# FindMe_Hub.net
KiCad netlist of a schematic drawn in EAGLE
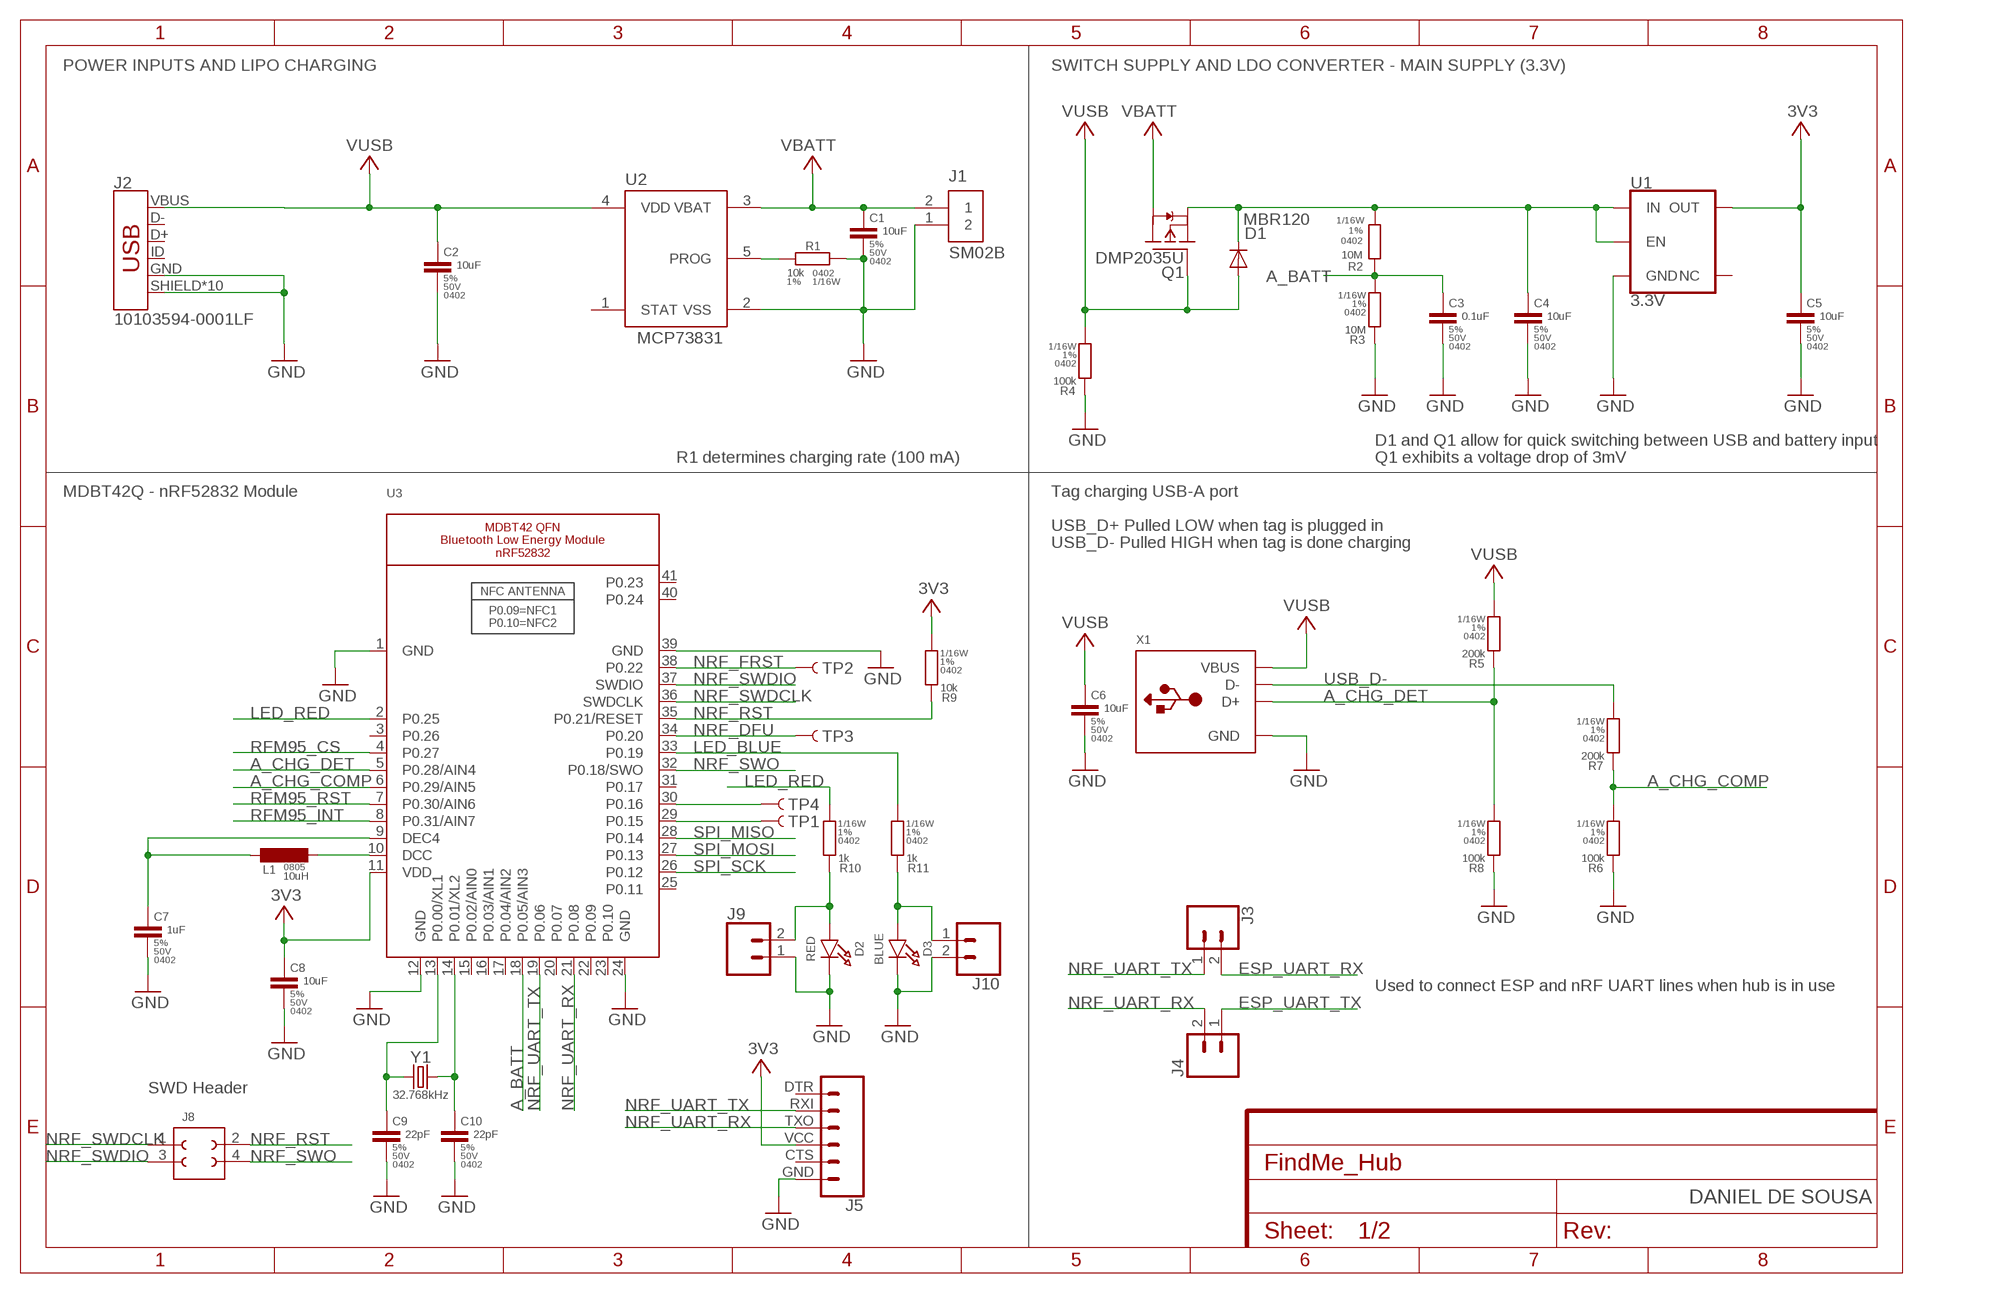
[diagram p0: schematic, sheet 1]
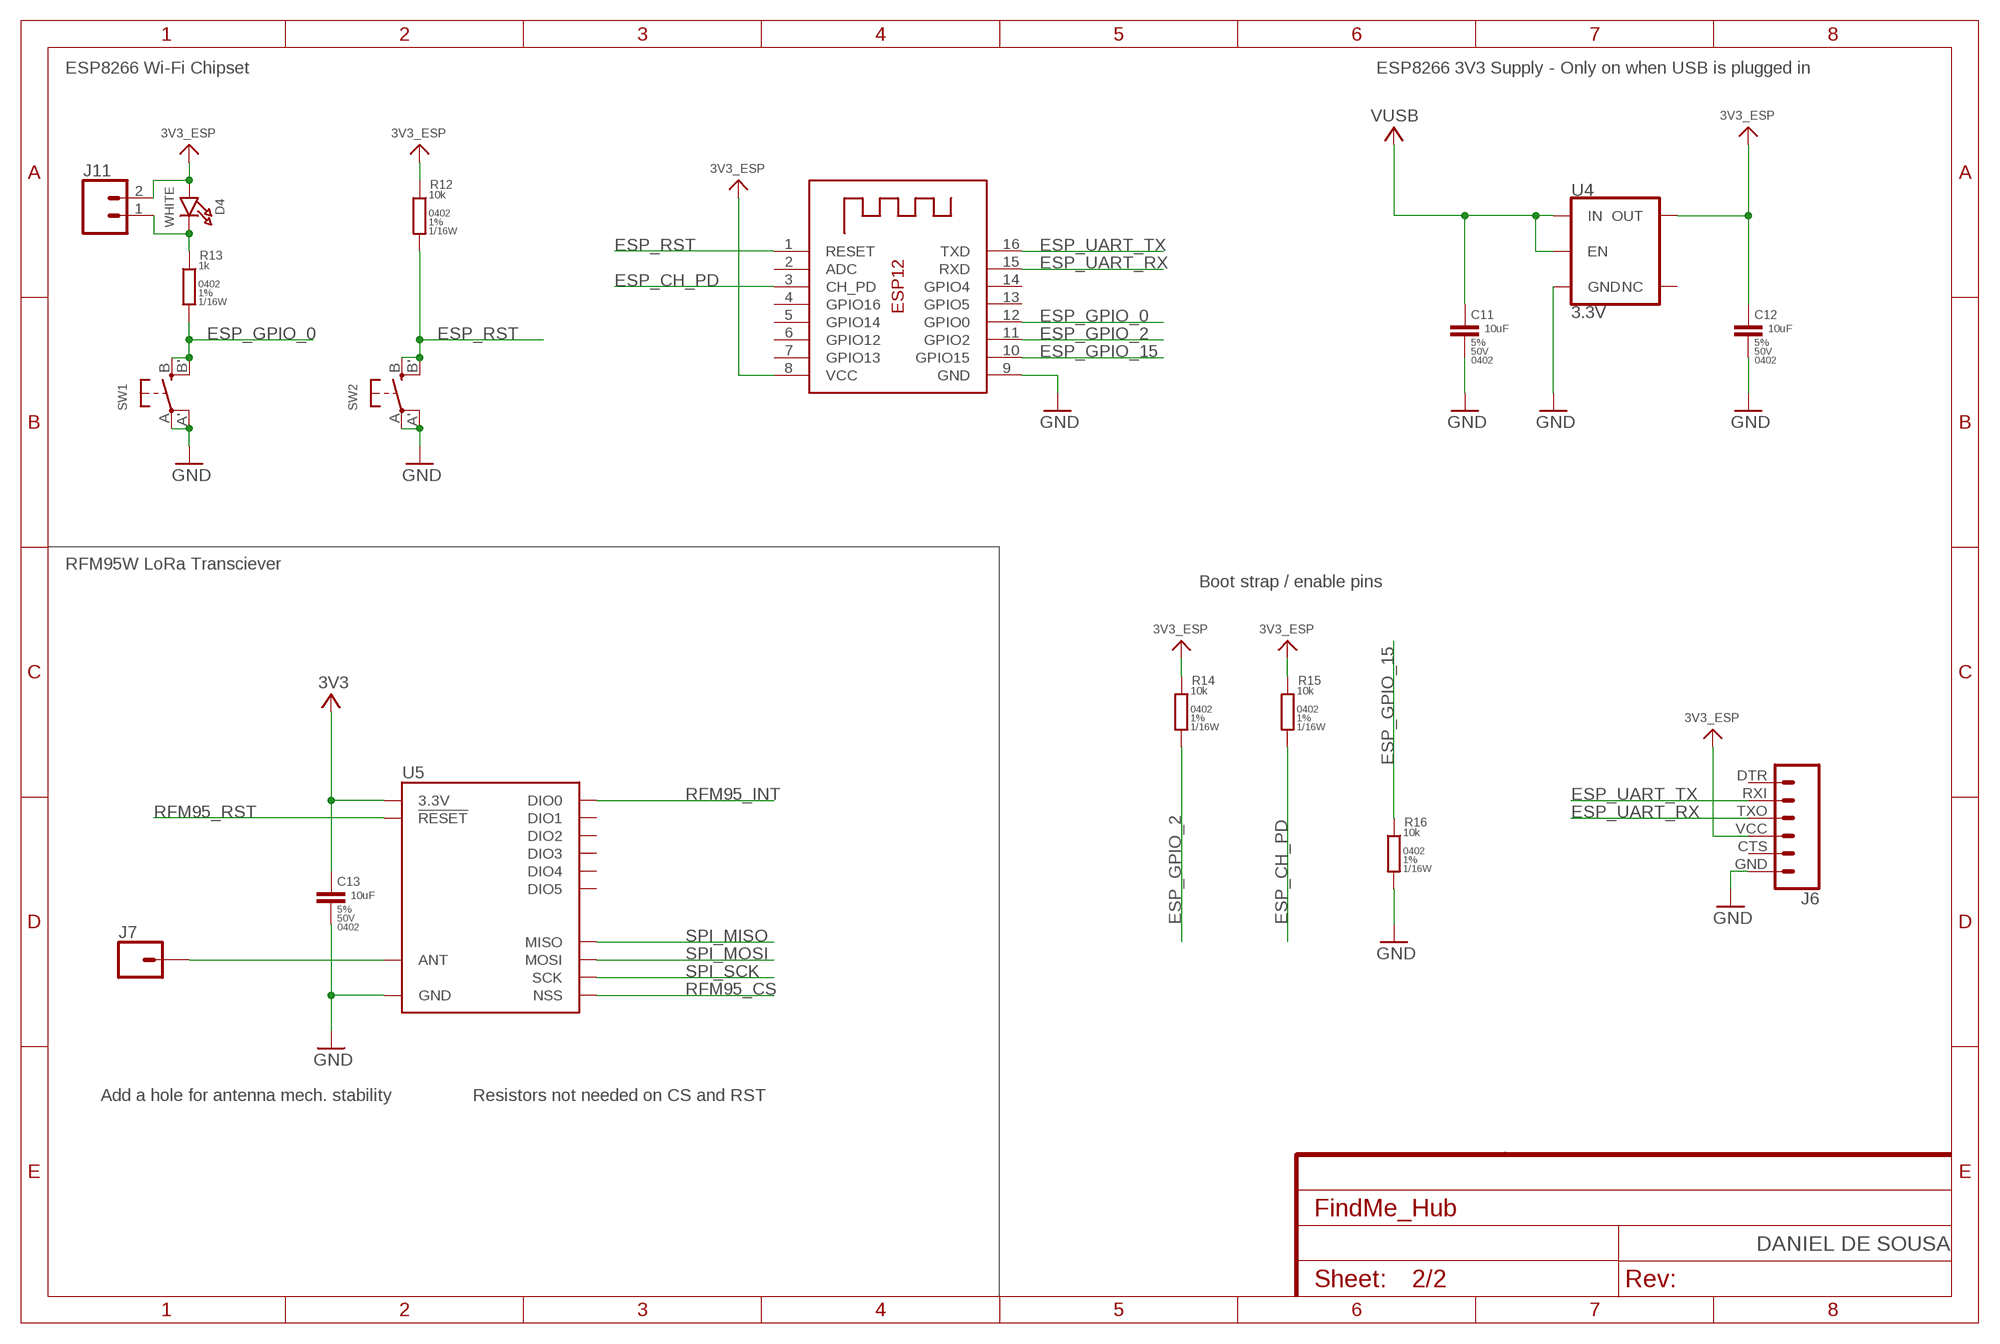
[diagram p1: schematic, sheet 2]

(export (version "E")
  (design (tool "Eeschema 10.0.6"))
  (components
    (comp (ref "C1")
      (value "10uF")
      (footprint "eagle-import:C0402_MURATA_GRM15-GJM15")
      (fields (field (name "TOLERANCE") "5%"))
      (libsource (lib "eagle-import") (part "C-EUC0402_MURATA_GRM15-GJM15"))
    )
    (comp (ref "C2")
      (value "10uF")
      (footprint "eagle-import:C0402_MURATA_GRM15-GJM15")
      (fields (field (name "TOLERANCE") "5%"))
      (libsource (lib "eagle-import") (part "C-EUC0402_MURATA_GRM15-GJM15"))
    )
    (comp (ref "C3")
      (value "0.1uF")
      (footprint "eagle-import:C0402_MURATA_GRM15-GJM15")
      (fields (field (name "TOLERANCE") "5%"))
      (libsource (lib "eagle-import") (part "C-EUC0402_MURATA_GRM15-GJM15"))
    )
    (comp (ref "C4")
      (value "10uF")
      (footprint "eagle-import:C0402_MURATA_GRM15-GJM15")
      (fields (field (name "TOLERANCE") "5%"))
      (libsource (lib "eagle-import") (part "C-EUC0402_MURATA_GRM15-GJM15"))
    )
    (comp (ref "C5")
      (value "10uF")
      (footprint "eagle-import:C0402_MURATA_GRM15-GJM15")
      (fields (field (name "TOLERANCE") "5%"))
      (libsource (lib "eagle-import") (part "C-EUC0402_MURATA_GRM15-GJM15"))
    )
    (comp (ref "C6")
      (value "10uF")
      (footprint "eagle-import:C0402_MURATA_GRM15-GJM15")
      (fields (field (name "TOLERANCE") "5%"))
      (libsource (lib "eagle-import") (part "C-EUC0402_MURATA_GRM15-GJM15"))
    )
    (comp (ref "C7")
      (value "1uF")
      (footprint "eagle-import:C0402_MURATA_GRM15-GJM15")
      (fields (field (name "TOLERANCE") "5%"))
      (libsource (lib "eagle-import") (part "C-EUC0402_MURATA_GRM15-GJM15"))
    )
    (comp (ref "C8")
      (value "10uF")
      (footprint "eagle-import:C0402_MURATA_GRM15-GJM15")
      (fields (field (name "TOLERANCE") "5%"))
      (libsource (lib "eagle-import") (part "C-EUC0402_MURATA_GRM15-GJM15"))
    )
    (comp (ref "C9")
      (value "22pF")
      (footprint "eagle-import:C0402_MURATA_GRM15-GJM15")
      (fields (field (name "RATING") "50V") (field (name "TOLERANCE") "5%") (field (name "PACKAGE") "0402"))
      (libsource (lib "eagle-import") (part "C-EUC0402_MURATA_GRM15-GJM15"))
    )
    (comp (ref "C10")
      (value "22pF")
      (footprint "eagle-import:C0402_MURATA_GRM15-GJM15")
      (fields (field (name "RATING") "50V") (field (name "TOLERANCE") "5%") (field (name "PACKAGE") "0402"))
      (libsource (lib "eagle-import") (part "C-EUC0402_MURATA_GRM15-GJM15"))
    )
    (comp (ref "D1")
      (value "MBR120")
      (footprint "eagle-import:SOD-123FL")
      (fields (field (name "PARTNO") "AS-ITM-00111"))
      (libsource (lib "eagle-import") (part "AS-ITM-00111"))
    )
    (comp (ref "D2")
      (value "RED")
      (footprint "eagle-import:CHIPLED_0805_NOOUTLINE")
      (libsource (lib "eagle-import") (part "LED0805_NOOUTLINE"))
    )
    (comp (ref "D3")
      (value "BLUE")
      (footprint "eagle-import:CHIPLED_0805_NOOUTLINE")
      (libsource (lib "eagle-import") (part "LED0805_NOOUTLINE"))
    )
    (comp (ref "J1")
      (value "SM02B")
      (footprint "eagle-import:JST_SH_2X1")
      (fields (field (name "PARTNO") "AS-ITM-00231"))
      (libsource (lib "eagle-import") (part "AS-ITM-00231"))
    )
    (comp (ref "J2")
      (value "10103594-0001LF")
      (footprint "eagle-import:USB-MICROB-PTH-MILL")
      (libsource (lib "eagle-import") (part "USB_MICRO-B_HALF_PTH_MILL"))
    )
    (comp (ref "J3")
      (value "CONN_02")
      (footprint "eagle-import:1X02")
      (libsource (lib "eagle-import") (part "CONN_02"))
    )
    (comp (ref "J4")
      (value "CONN_02")
      (footprint "eagle-import:1X02")
      (libsource (lib "eagle-import") (part "CONN_02"))
    )
    (comp (ref "J5")
      (value "6_PIN_SERIAL_CABLEPTH")
      (footprint "eagle-import:FTDI_BASIC")
      (libsource (lib "eagle-import") (part "6_PIN_SERIAL_CABLEPTH"))
    )
    (comp (ref "J8")
      (value "610X0421121")
      (footprint "eagle-import:610X0421121")
      (libsource (lib "eagle-import") (part "610X0421121"))
    )
    (comp (ref "J9")
      (value "CONN_02")
      (footprint "eagle-import:1X02")
      (libsource (lib "eagle-import") (part "CONN_02"))
    )
    (comp (ref "J10")
      (value "CONN_02")
      (footprint "eagle-import:1X02")
      (libsource (lib "eagle-import") (part "CONN_02"))
    )
    (comp (ref "L1")
      (value "10uH")
      (footprint "eagle-import:L0805_MURATA_LQM21")
      (fields (field (name "PACKAGE") "0805") (field (name "TOLERANCE") "20%"))
      (libsource (lib "eagle-import") (part "LQM21PN1R0MC0D"))
    )
    (comp (ref "Q1")
      (value "DMP2035U")
      (footprint "eagle-import:SOT23")
      (fields (field (name "PARTNO") "AS-ITM-00024"))
      (libsource (lib "eagle-import") (part "AS-ITM-00024"))
    )
    (comp (ref "R1")
      (value "10k")
      (footprint "eagle-import:R0402_VISHAY_CRCW0402")
      (fields (field (name "TOLERANCE") "1%") (field (name "RATING") "1/16W") (field (name "PACKAGE") "0402"))
      (libsource (lib "eagle-import") (part "CRCW040210K0FKED"))
    )
    (comp (ref "R2")
      (value "10M")
      (footprint "eagle-import:R0402_VISHAY_CRCW0402")
      (fields (field (name "TOLERANCE") "1%") (field (name "RATING") "1/16W") (field (name "PACKAGE") "0402"))
      (libsource (lib "eagle-import") (part "CRCW04021M00FKED"))
    )
    (comp (ref "R3")
      (value "10M")
      (footprint "eagle-import:R0402_VISHAY_CRCW0402")
      (fields (field (name "TOLERANCE") "1%"))
      (libsource (lib "eagle-import") (part "CRCW04021M00FKED"))
    )
    (comp (ref "R4")
      (value "100k")
      (footprint "eagle-import:R0402_VISHAY_CRCW0402")
      (fields (field (name "TOLERANCE") "1%"))
      (libsource (lib "eagle-import") (part "CRCW04021M00FKED"))
    )
    (comp (ref "R5")
      (value "200k")
      (footprint "eagle-import:R0402_VISHAY_CRCW0402")
      (fields (field (name "TOLERANCE") "1%"))
      (libsource (lib "eagle-import") (part "CRCW04021M00FKED"))
    )
    (comp (ref "R6")
      (value "100k")
      (footprint "eagle-import:R0402_VISHAY_CRCW0402")
      (fields (field (name "TOLERANCE") "1%"))
      (libsource (lib "eagle-import") (part "CRCW04021M00FKED"))
    )
    (comp (ref "R7")
      (value "200k")
      (footprint "eagle-import:R0402_VISHAY_CRCW0402")
      (fields (field (name "TOLERANCE") "1%"))
      (libsource (lib "eagle-import") (part "CRCW04021M00FKED"))
    )
    (comp (ref "R8")
      (value "100k")
      (footprint "eagle-import:R0402_VISHAY_CRCW0402")
      (fields (field (name "TOLERANCE") "1%"))
      (libsource (lib "eagle-import") (part "CRCW04021M00FKED"))
    )
    (comp (ref "R9")
      (value "10k")
      (footprint "eagle-import:R0402_VISHAY_CRCW0402")
      (fields (field (name "TOLERANCE") "1%"))
      (libsource (lib "eagle-import") (part "CRCW040210K0FKED"))
    )
    (comp (ref "R10")
      (value "1k")
      (footprint "eagle-import:R0402_VISHAY_CRCW0402")
      (fields (field (name "TOLERANCE") "1%"))
      (libsource (lib "eagle-import") (part "CRCW040210K0FKED"))
    )
    (comp (ref "R11")
      (value "1k")
      (footprint "eagle-import:R0402_VISHAY_CRCW0402")
      (fields (field (name "TOLERANCE") "1%"))
      (libsource (lib "eagle-import") (part "CRCW040210K0FKED"))
    )
    (comp (ref "TP1")
      (value "TEST-POINT3X5")
      (footprint "eagle-import:PAD.03X.05")
      (libsource (lib "eagle-import") (part "TEST-POINT3X5"))
    )
    (comp (ref "TP2")
      (value "TEST-POINT3X5")
      (footprint "eagle-import:PAD.03X.05")
      (libsource (lib "eagle-import") (part "TEST-POINT3X5"))
    )
    (comp (ref "TP3")
      (value "TEST-POINT3X5")
      (footprint "eagle-import:PAD.03X.05")
      (libsource (lib "eagle-import") (part "TEST-POINT3X5"))
    )
    (comp (ref "TP4")
      (value "TEST-POINT3X5")
      (footprint "eagle-import:PAD.03X.05")
      (libsource (lib "eagle-import") (part "TEST-POINT3X5"))
    )
    (comp (ref "U1")
      (value "3.3V")
      (footprint "eagle-import:SOT23-5")
      (libsource (lib "eagle-import") (part "V_REG_AP2112K-3.3V"))
    )
    (comp (ref "U2")
      (value "MCP73831")
      (footprint "eagle-import:SOT-23")
      (fields (field (name "PARTNO") "AS-ITM-00136"))
      (libsource (lib "eagle-import") (part "AS-ITM-00136"))
    )
    (comp (ref "U3")
      (value "NRF52832_MODULE_MDBT42")
      (footprint "eagle-import:BLE_MODULE_RAYTAC_MDBT42")
      (libsource (lib "eagle-import") (part "NRF52832_MODULE_MDBT42"))
    )
    (comp (ref "X1")
      (value "USB_TYPEAPTHFML")
      (footprint "eagle-import:USB_HOST-PTH")
      (libsource (lib "eagle-import") (part "USB_TYPEAPTHFML"))
    )
    (comp (ref "Y1")
      (value "32.768kHz")
      (footprint "eagle-import:CRYSTAL-SMD-3.2X1.5MM")
      (libsource (lib "eagle-import") (part "CRYSTAL-32.768KHZSMD-3.2X1.5"))
    )
    (comp (ref "C11")
      (value "10uF")
      (footprint "eagle-import:C0402_MURATA_GRM15-GJM15")
      (fields (field (name "TOLERANCE") "5%"))
      (libsource (lib "eagle-import") (part "C-EUC0402_MURATA_GRM15-GJM15"))
    )
    (comp (ref "C12")
      (value "10uF")
      (footprint "eagle-import:C0402_MURATA_GRM15-GJM15")
      (fields (field (name "TOLERANCE") "5%"))
      (libsource (lib "eagle-import") (part "C-EUC0402_MURATA_GRM15-GJM15"))
    )
    (comp (ref "C13")
      (value "10uF")
      (footprint "eagle-import:C0402_MURATA_GRM15-GJM15")
      (fields (field (name "TOLERANCE") "5%"))
      (libsource (lib "eagle-import") (part "C-EUC0402_MURATA_GRM15-GJM15"))
    )
    (comp (ref "D4")
      (value "WHITE")
      (footprint "eagle-import:CHIPLED_0805_NOOUTLINE")
      (libsource (lib "eagle-import") (part "LED0805_NOOUTLINE"))
    )
    (comp (ref "J6")
      (value "6_PIN_SERIAL_CABLEPTH")
      (footprint "eagle-import:FTDI_BASIC")
      (libsource (lib "eagle-import") (part "6_PIN_SERIAL_CABLEPTH"))
    )
    (comp (ref "J7")
      (value "CONN_01PTH_NO_SILK_YES_STOP")
      (footprint "eagle-import:1X01_NO_SILK")
      (libsource (lib "eagle-import") (part "CONN_01PTH_NO_SILK_YES_STOP"))
    )
    (comp (ref "J11")
      (value "CONN_02")
      (footprint "eagle-import:1X02")
      (libsource (lib "eagle-import") (part "CONN_02"))
    )
    (comp (ref "R12")
      (value "10k")
      (footprint "eagle-import:R0402_VISHAY_CRCW0402")
      (fields (field (name "TOLERANCE") "1%"))
      (libsource (lib "eagle-import") (part "CRCW04021M00FKED"))
    )
    (comp (ref "R13")
      (value "1k")
      (footprint "eagle-import:R0402_VISHAY_CRCW0402")
      (fields (field (name "TOLERANCE") "1%"))
      (libsource (lib "eagle-import") (part "CRCW04021M00FKED"))
    )
    (comp (ref "R14")
      (value "10k")
      (footprint "eagle-import:R0402_VISHAY_CRCW0402")
      (fields (field (name "TOLERANCE") "1%"))
      (libsource (lib "eagle-import") (part "CRCW04021M00FKED"))
    )
    (comp (ref "R15")
      (value "10k")
      (footprint "eagle-import:R0402_VISHAY_CRCW0402")
      (fields (field (name "TOLERANCE") "1%"))
      (libsource (lib "eagle-import") (part "CRCW04021M00FKED"))
    )
    (comp (ref "R16")
      (value "10k")
      (footprint "eagle-import:R0402_VISHAY_CRCW0402")
      (fields (field (name "TOLERANCE") "1%"))
      (libsource (lib "eagle-import") (part "CRCW04021M00FKED"))
    )
    (comp (ref "SW1")
      (value "SWITCH_TACT_SMT4.6X2.8")
      (footprint "eagle-import:BTN_KMR2_4.6X2.8")
      (libsource (lib "eagle-import") (part "SWITCH_TACT_SMT4.6X2.8"))
    )
    (comp (ref "SW2")
      (value "SWITCH_TACT_SMT4.6X2.8")
      (footprint "eagle-import:BTN_KMR2_4.6X2.8")
      (libsource (lib "eagle-import") (part "SWITCH_TACT_SMT4.6X2.8"))
    )
    (comp (ref "U4")
      (value "3.3V")
      (footprint "eagle-import:SOT23-5")
      (libsource (lib "eagle-import") (part "V_REG_AP2112K-3.3V"))
    )
    (comp (ref "U5")
      (value "RFM95W")
      (footprint "eagle-import:RFM95_96_97_98W")
      (libsource (lib "eagle-import") (part "RFM95W"))
    )
    (comp (ref "X2")
      (value "ESP-12")
      (footprint "eagle-import:ESP-12")
      (libsource (lib "eagle-import") (part "ESP-12"))
    )
  )
  (nets
    (net (code "1") (name "+3V3") (class "Default")
      (node (ref "C13") (pin "1") (pinfunction "1_1") (pintype "passive"))
      (node (ref "C5") (pin "1") (pinfunction "1_1") (pintype "passive"))
      (node (ref "C8") (pin "1") (pinfunction "1_1") (pintype "passive"))
      (node (ref "J5") (pin "VCC") (pinfunction "4_VCC") (pintype "passive"))
      (node (ref "R9") (pin "2") (pinfunction "2_2") (pintype "passive"))
      (node (ref "U1") (pin "5") (pinfunction "OUT_5") (pintype "passive"))
      (node (ref "U3") (pin "11") (pinfunction "VDD_11") (pintype "bidirectional"))
      (node (ref "U5") (pin "3.3V") (pinfunction "3.3V_3.3V") (pintype "bidirectional"))
    )
    (net (code "2") (name "A_BATT") (class "Default")
      (node (ref "C3") (pin "1") (pinfunction "1_1") (pintype "passive"))
      (node (ref "R2") (pin "1") (pinfunction "1_1") (pintype "passive"))
      (node (ref "R3") (pin "2") (pinfunction "2_2") (pintype "passive"))
      (node (ref "U3") (pin "18") (pinfunction "P0.05/AIN3_18") (pintype "bidirectional"))
    )
    (net (code "3") (name "A_CHG_COMP") (class "Default")
      (node (ref "R6") (pin "2") (pinfunction "2_2") (pintype "passive"))
      (node (ref "R7") (pin "1") (pinfunction "1_1") (pintype "passive"))
      (node (ref "U3") (pin "6") (pinfunction "P0.29/AIN5_6") (pintype "bidirectional"))
    )
    (net (code "4") (name "A_CHG_DET") (class "Default")
      (node (ref "R5") (pin "1") (pinfunction "1_1") (pintype "passive"))
      (node (ref "R8") (pin "2") (pinfunction "2_2") (pintype "passive"))
      (node (ref "U3") (pin "5") (pinfunction "P0.28/AIN4_5") (pintype "bidirectional"))
      (node (ref "X1") (pin "D+") (pinfunction "D+_D+") (pintype "bidirectional"))
    )
    (net (code "5") (name "ESP_CH_PD") (class "Default")
      (node (ref "R15") (pin "2") (pinfunction "2_2") (pintype "passive"))
      (node (ref "X2") (pin "3") (pinfunction "CH_PD_3") (pintype "input"))
    )
    (net (code "6") (name "ESP_GPIO_0") (class "Default")
      (node (ref "R13") (pin "2") (pinfunction "2_2") (pintype "passive"))
      (node (ref "SW1") (pin "B") (pinfunction "S_B") (pintype "passive"))
      (node (ref "SW1") (pin "B'") (pinfunction "S1_B'") (pintype "passive"))
      (node (ref "X2") (pin "12") (pinfunction "GPIO0_12") (pintype "bidirectional"))
    )
    (net (code "7") (name "ESP_GPIO_2") (class "Default")
      (node (ref "R14") (pin "2") (pinfunction "2_2") (pintype "passive"))
      (node (ref "X2") (pin "11") (pinfunction "GPIO2_11") (pintype "bidirectional"))
    )
    (net (code "8") (name "ESP_GPIO_15") (class "Default")
      (node (ref "R16") (pin "1") (pinfunction "1_1") (pintype "passive"))
      (node (ref "X2") (pin "10") (pinfunction "GPIO15_10") (pintype "bidirectional"))
    )
    (net (code "9") (name "ESP_RST") (class "Default")
      (node (ref "R12") (pin "2") (pinfunction "2_2") (pintype "passive"))
      (node (ref "SW2") (pin "B") (pinfunction "S_B") (pintype "passive"))
      (node (ref "SW2") (pin "B'") (pinfunction "S1_B'") (pintype "passive"))
      (node (ref "X2") (pin "1") (pinfunction "RESET_1") (pintype "input"))
    )
    (net (code "10") (name "ESP_UART_RX") (class "Default")
      (node (ref "J3") (pin "2") (pinfunction "2_2") (pintype "passive"))
      (node (ref "J6") (pin "TXO") (pinfunction "3_TXO") (pintype "passive"))
      (node (ref "X2") (pin "15") (pinfunction "RXD_15") (pintype "input"))
    )
    (net (code "11") (name "ESP_UART_TX") (class "Default")
      (node (ref "J4") (pin "1") (pinfunction "1_1") (pintype "passive"))
      (node (ref "J6") (pin "RXI") (pinfunction "2_RXI") (pintype "passive"))
      (node (ref "X2") (pin "16") (pinfunction "TXD_16") (pintype "output"))
    )
    (net (code "12") (name "GND") (class "Default")
      (node (ref "C1") (pin "2") (pinfunction "2_2") (pintype "passive"))
      (node (ref "C10") (pin "2") (pinfunction "2_2") (pintype "passive"))
      (node (ref "C11") (pin "2") (pinfunction "2_2") (pintype "passive"))
      (node (ref "C12") (pin "2") (pinfunction "2_2") (pintype "passive"))
      (node (ref "C13") (pin "2") (pinfunction "2_2") (pintype "passive"))
      (node (ref "C2") (pin "2") (pinfunction "2_2") (pintype "passive"))
      (node (ref "C3") (pin "2") (pinfunction "2_2") (pintype "passive"))
      (node (ref "C4") (pin "2") (pinfunction "2_2") (pintype "passive"))
      (node (ref "C5") (pin "2") (pinfunction "2_2") (pintype "passive"))
      (node (ref "C6") (pin "2") (pinfunction "2_2") (pintype "passive"))
      (node (ref "C7") (pin "2") (pinfunction "2_2") (pintype "passive"))
      (node (ref "C8") (pin "2") (pinfunction "2_2") (pintype "passive"))
      (node (ref "C9") (pin "2") (pinfunction "2_2") (pintype "passive"))
      (node (ref "D2") (pin "C") (pinfunction "C_C") (pintype "passive"))
      (node (ref "D3") (pin "C") (pinfunction "C_C") (pintype "passive"))
      (node (ref "J1") (pin "1") (pinfunction "2_1") (pintype "bidirectional"))
      (node (ref "J10") (pin "2") (pinfunction "2_2") (pintype "passive"))
      (node (ref "J2") (pin "GND") (pinfunction "GND_GND") (pintype "power_in"))
      (node (ref "J2") (pin "SHIELD") (pinfunction "SHIELD_SHIELD") (pintype "bidirectional"))
      (node (ref "J2") (pin "SHIELD10") (pinfunction "SHIELD_SHIELD10") (pintype "bidirectional"))
      (node (ref "J2") (pin "SHIELD2") (pinfunction "SHIELD_SHIELD2") (pintype "bidirectional"))
      (node (ref "J2") (pin "SHIELD3") (pinfunction "SHIELD_SHIELD3") (pintype "bidirectional"))
      (node (ref "J2") (pin "SHIELD4") (pinfunction "SHIELD_SHIELD4") (pintype "bidirectional"))
      (node (ref "J2") (pin "SHIELD5") (pinfunction "SHIELD_SHIELD5") (pintype "bidirectional"))
      (node (ref "J2") (pin "SHIELD6") (pinfunction "SHIELD_SHIELD6") (pintype "bidirectional"))
      (node (ref "J2") (pin "SHIELD7") (pinfunction "SHIELD_SHIELD7") (pintype "bidirectional"))
      (node (ref "J2") (pin "SHIELD8") (pinfunction "SHIELD_SHIELD8") (pintype "bidirectional"))
      (node (ref "J2") (pin "SHIELD9") (pinfunction "SHIELD_SHIELD9") (pintype "bidirectional"))
      (node (ref "J5") (pin "GND") (pinfunction "6_GND") (pintype "passive"))
      (node (ref "J6") (pin "GND") (pinfunction "6_GND") (pintype "passive"))
      (node (ref "J9") (pin "1") (pinfunction "1_1") (pintype "passive"))
      (node (ref "R1") (pin "1") (pinfunction "1_1") (pintype "passive"))
      (node (ref "R16") (pin "2") (pinfunction "2_2") (pintype "passive"))
      (node (ref "R3") (pin "1") (pinfunction "1_1") (pintype "passive"))
      (node (ref "R4") (pin "1") (pinfunction "1_1") (pintype "passive"))
      (node (ref "R6") (pin "1") (pinfunction "1_1") (pintype "passive"))
      (node (ref "R8") (pin "1") (pinfunction "1_1") (pintype "passive"))
      (node (ref "SW1") (pin "A") (pinfunction "P_A") (pintype "passive"))
      (node (ref "SW1") (pin "A'") (pinfunction "P1_A'") (pintype "passive"))
      (node (ref "SW2") (pin "A") (pinfunction "P_A") (pintype "passive"))
      (node (ref "SW2") (pin "A'") (pinfunction "P1_A'") (pintype "passive"))
      (node (ref "U1") (pin "2") (pinfunction "GND_2") (pintype "input"))
      (node (ref "U2") (pin "2") (pinfunction "VSS_2") (pintype "bidirectional"))
      (node (ref "U3") (pin "1") (pinfunction "GND_1") (pintype "bidirectional"))
      (node (ref "U3") (pin "12") (pinfunction "GND_12") (pintype "bidirectional"))
      (node (ref "U3") (pin "24") (pinfunction "GND_24") (pintype "bidirectional"))
      (node (ref "U3") (pin "39") (pinfunction "GND_39") (pintype "bidirectional"))
      (node (ref "U4") (pin "2") (pinfunction "GND_2") (pintype "input"))
      (node (ref "U5") (pin "GND@1") (pinfunction "GND_GND@1") (pintype "bidirectional"))
      (node (ref "U5") (pin "GND@2") (pinfunction "GND_GND@2") (pintype "bidirectional"))
      (node (ref "U5") (pin "GND@3") (pinfunction "GND_GND@3") (pintype "bidirectional"))
      (node (ref "X1") (pin "GND") (pinfunction "GND_GND") (pintype "power_in"))
      (node (ref "X2") (pin "9") (pinfunction "GND_9") (pintype "power_in"))
    )
    (net (code "13") (name "LED_BLUE") (class "Default")
      (node (ref "R11") (pin "2") (pinfunction "2_2") (pintype "passive"))
      (node (ref "U3") (pin "33") (pinfunction "P0.19_33") (pintype "bidirectional"))
    )
    (net (code "14") (name "LED_RED") (class "Default")
      (node (ref "R10") (pin "2") (pinfunction "2_2") (pintype "passive"))
      (node (ref "U3") (pin "2") (pinfunction "P0.25_2") (pintype "bidirectional"))
    )
    (net (code "15") (name "NRF_DFU") (class "Default")
      (node (ref "TP3") (pin "P$1") (pinfunction "1_P$1") (pintype "bidirectional"))
      (node (ref "U3") (pin "34") (pinfunction "P0.20_34") (pintype "bidirectional"))
    )
    (net (code "16") (name "NRF_FRST") (class "Default")
      (node (ref "TP2") (pin "P$1") (pinfunction "1_P$1") (pintype "bidirectional"))
      (node (ref "U3") (pin "38") (pinfunction "P0.22_38") (pintype "bidirectional"))
    )
    (net (code "17") (name "NRF_RST") (class "Default")
      (node (ref "J8") (pin "2") (pinfunction "4_2") (pintype "passive"))
      (node (ref "R9") (pin "1") (pinfunction "1_1") (pintype "passive"))
      (node (ref "U3") (pin "35") (pinfunction "P0.21/RESET_35") (pintype "bidirectional"))
    )
    (net (code "18") (name "NRF_SWDCLK") (class "Default")
      (node (ref "J8") (pin "1") (pinfunction "1_1") (pintype "passive"))
      (node (ref "U3") (pin "36") (pinfunction "SWDCLK_36") (pintype "bidirectional"))
    )
    (net (code "19") (name "NRF_SWDIO") (class "Default")
      (node (ref "J8") (pin "3") (pinfunction "2_3") (pintype "passive"))
      (node (ref "U3") (pin "37") (pinfunction "SWDIO_37") (pintype "bidirectional"))
    )
    (net (code "20") (name "NRF_SWO") (class "Default")
      (node (ref "J8") (pin "4") (pinfunction "3_4") (pintype "passive"))
      (node (ref "U3") (pin "32") (pinfunction "P0.18/SWO_32") (pintype "bidirectional"))
    )
    (net (code "21") (name "NRF_UART_RX") (class "Default")
      (node (ref "J4") (pin "2") (pinfunction "2_2") (pintype "passive"))
      (node (ref "J5") (pin "TXO") (pinfunction "3_TXO") (pintype "passive"))
      (node (ref "U3") (pin "21") (pinfunction "P0.08_21") (pintype "bidirectional"))
    )
    (net (code "22") (name "NRF_UART_TX") (class "Default")
      (node (ref "J3") (pin "1") (pinfunction "1_1") (pintype "passive"))
      (node (ref "J5") (pin "RXI") (pinfunction "2_RXI") (pintype "passive"))
      (node (ref "U3") (pin "19") (pinfunction "P0.06_19") (pintype "bidirectional"))
    )
    (net (code "23") (name "Net-(D2-PadA)") (class "Default")
      (node (ref "D2") (pin "A") (pinfunction "A_A") (pintype "passive"))
      (node (ref "J9") (pin "2") (pinfunction "2_2") (pintype "passive"))
      (node (ref "R10") (pin "1") (pinfunction "1_1") (pintype "passive"))
    )
    (net (code "24") (name "Net-(D3-PadA)") (class "Default")
      (node (ref "D3") (pin "A") (pinfunction "A_A") (pintype "passive"))
      (node (ref "J10") (pin "1") (pinfunction "1_1") (pintype "passive"))
      (node (ref "R11") (pin "1") (pinfunction "1_1") (pintype "passive"))
    )
    (net (code "25") (name "Net-(D4-PadC)") (class "Default")
      (node (ref "D4") (pin "C") (pinfunction "C_C") (pintype "passive"))
      (node (ref "J11") (pin "1") (pinfunction "1_1") (pintype "passive"))
      (node (ref "R13") (pin "1") (pinfunction "1_1") (pintype "passive"))
    )
    (net (code "26") (name "Net-(J7-Pad1)") (class "Default")
      (node (ref "J7") (pin "1") (pinfunction "1_1") (pintype "passive"))
      (node (ref "U5") (pin "ANT") (pinfunction "ANT_ANT") (pintype "bidirectional"))
    )
    (net (code "27") (name "Net-(L1-1)") (class "Default")
      (node (ref "C7") (pin "1") (pinfunction "1_1") (pintype "passive"))
      (node (ref "L1") (pin "P$1") (pinfunction "1_P$1") (pintype "passive"))
      (node (ref "U3") (pin "9") (pinfunction "DEC4_9") (pintype "bidirectional"))
    )
    (net (code "28") (name "Net-(L1-2)") (class "Default")
      (node (ref "L1") (pin "P$2") (pinfunction "2_P$2") (pintype "passive"))
      (node (ref "U3") (pin "10") (pinfunction "DCC_10") (pintype "bidirectional"))
    )
    (net (code "29") (name "Net-(Q1-S)") (class "Default")
      (node (ref "C4") (pin "1") (pinfunction "1_1") (pintype "passive"))
      (node (ref "D1") (pin "C") (pinfunction "C_C") (pintype "passive"))
      (node (ref "Q1") (pin "E") (pinfunction "S_E") (pintype "passive"))
      (node (ref "R2") (pin "2") (pinfunction "2_2") (pintype "passive"))
      (node (ref "U1") (pin "1") (pinfunction "IN_1") (pintype "input"))
      (node (ref "U1") (pin "3") (pinfunction "EN_3") (pintype "input"))
    )
    (net (code "30") (name "Net-(TP1-1)") (class "Default")
      (node (ref "TP1") (pin "P$1") (pinfunction "1_P$1") (pintype "bidirectional"))
      (node (ref "U3") (pin "29") (pinfunction "P0.15_29") (pintype "bidirectional"))
    )
    (net (code "31") (name "Net-(TP4-1)") (class "Default")
      (node (ref "TP4") (pin "P$1") (pinfunction "1_P$1") (pintype "bidirectional"))
      (node (ref "U3") (pin "30") (pinfunction "P0.16_30") (pintype "bidirectional"))
    )
    (net (code "32") (name "Net-(U2-PROG)") (class "Default")
      (node (ref "R1") (pin "2") (pinfunction "2_2") (pintype "passive"))
      (node (ref "U2") (pin "5") (pinfunction "PROG_5") (pintype "bidirectional"))
    )
    (net (code "33") (name "Net-(U3-P0.00{slash}XL1)") (class "Default")
      (node (ref "C9") (pin "1") (pinfunction "1_1") (pintype "passive"))
      (node (ref "U3") (pin "13") (pinfunction "P0.00/XL1_13") (pintype "bidirectional"))
      (node (ref "Y1") (pin "P$1") (pinfunction "1_P$1") (pintype "passive"))
    )
    (net (code "34") (name "Net-(U3-P0.01{slash}XL2)") (class "Default")
      (node (ref "C10") (pin "1") (pinfunction "1_1") (pintype "passive"))
      (node (ref "U3") (pin "14") (pinfunction "P0.01/XL2_14") (pintype "bidirectional"))
      (node (ref "Y1") (pin "P$2") (pinfunction "2_P$2") (pintype "passive"))
    )
    (net (code "35") (name "RFM95_CS") (class "Default")
      (node (ref "U3") (pin "4") (pinfunction "P0.27_4") (pintype "bidirectional"))
      (node (ref "U5") (pin "NSS") (pinfunction "NSS_NSS") (pintype "bidirectional"))
    )
    (net (code "36") (name "RFM95_INT") (class "Default")
      (node (ref "U3") (pin "8") (pinfunction "P0.31/AIN7_8") (pintype "bidirectional"))
      (node (ref "U5") (pin "DIO0") (pinfunction "DIO0_DIO0") (pintype "bidirectional"))
    )
    (net (code "37") (name "RFM95_RST") (class "Default")
      (node (ref "U3") (pin "7") (pinfunction "P0.30/AIN6_7") (pintype "bidirectional"))
      (node (ref "U5") (pin "!RESET") (pinfunction "~{RESET}_!RESET") (pintype "bidirectional"))
    )
    (net (code "38") (name "SPI_MISO") (class "Default")
      (node (ref "U3") (pin "28") (pinfunction "P0.14_28") (pintype "bidirectional"))
      (node (ref "U5") (pin "MISO") (pinfunction "MISO_MISO") (pintype "bidirectional"))
    )
    (net (code "39") (name "SPI_MOSI") (class "Default")
      (node (ref "U3") (pin "27") (pinfunction "P0.13_27") (pintype "bidirectional"))
      (node (ref "U5") (pin "MOSI") (pinfunction "MOSI_MOSI") (pintype "bidirectional"))
    )
    (net (code "40") (name "SPI_SCK") (class "Default")
      (node (ref "U3") (pin "26") (pinfunction "P0.12_26") (pintype "bidirectional"))
      (node (ref "U5") (pin "SCK") (pinfunction "SCK_SCK") (pintype "bidirectional"))
    )
    (net (code "41") (name "USB_D-") (class "Default")
      (node (ref "R7") (pin "2") (pinfunction "2_2") (pintype "passive"))
      (node (ref "X1") (pin "D-") (pinfunction "D-_D-") (pintype "bidirectional"))
    )
    (net (code "42") (name "VBATT") (class "Default")
      (node (ref "C1") (pin "1") (pinfunction "1_1") (pintype "passive"))
      (node (ref "J1") (pin "2") (pinfunction "1_2") (pintype "bidirectional"))
      (node (ref "Q1") (pin "C") (pinfunction "D_C") (pintype "passive"))
      (node (ref "U2") (pin "3") (pinfunction "VBAT_3") (pintype "bidirectional"))
    )
    (net (code "43") (name "VCCIO") (class "Default")
      (node (ref "C12") (pin "1") (pinfunction "1_1") (pintype "passive"))
      (node (ref "D4") (pin "A") (pinfunction "A_A") (pintype "passive"))
      (node (ref "J11") (pin "2") (pinfunction "2_2") (pintype "passive"))
      (node (ref "J6") (pin "VCC") (pinfunction "4_VCC") (pintype "passive"))
      (node (ref "R12") (pin "1") (pinfunction "1_1") (pintype "passive"))
      (node (ref "R14") (pin "1") (pinfunction "1_1") (pintype "passive"))
      (node (ref "R15") (pin "1") (pinfunction "1_1") (pintype "passive"))
      (node (ref "U4") (pin "5") (pinfunction "OUT_5") (pintype "passive"))
      (node (ref "X2") (pin "8") (pinfunction "VCC_8") (pintype "power_in"))
    )
    (net (code "44") (name "VUSB") (class "Default")
      (node (ref "C11") (pin "1") (pinfunction "1_1") (pintype "passive"))
      (node (ref "C2") (pin "1") (pinfunction "1_1") (pintype "passive"))
      (node (ref "C6") (pin "1") (pinfunction "1_1") (pintype "passive"))
      (node (ref "D1") (pin "A") (pinfunction "A_A") (pintype "passive"))
      (node (ref "J2") (pin "VBUS") (pinfunction "VBUS_VBUS") (pintype "power_in"))
      (node (ref "Q1") (pin "B") (pinfunction "G_B") (pintype "passive"))
      (node (ref "R4") (pin "2") (pinfunction "2_2") (pintype "passive"))
      (node (ref "R5") (pin "2") (pinfunction "2_2") (pintype "passive"))
      (node (ref "U2") (pin "4") (pinfunction "VDD_4") (pintype "bidirectional"))
      (node (ref "U4") (pin "1") (pinfunction "IN_1") (pintype "input"))
      (node (ref "U4") (pin "3") (pinfunction "EN_3") (pintype "input"))
      (node (ref "X1") (pin "VBUS") (pinfunction "VBUS_VBUS") (pintype "power_in"))
    )
    (net (code "45") (name "unconnected-(J2-PadD+)") (class "Default")
      (node (ref "J2") (pin "D+") (pinfunction "D+_D+") (pintype "bidirectional"))
    )
    (net (code "46") (name "unconnected-(J2-PadD-)") (class "Default")
      (node (ref "J2") (pin "D-") (pinfunction "D-_D-") (pintype "bidirectional"))
    )
    (net (code "47") (name "unconnected-(J2-PadID)") (class "Default")
      (node (ref "J2") (pin "ID") (pinfunction "ID_ID") (pintype "bidirectional"))
    )
    (net (code "48") (name "unconnected-(J5-1-PadDTR)") (class "Default")
      (node (ref "J5") (pin "DTR") (pinfunction "1_DTR") (pintype "passive"))
    )
    (net (code "49") (name "unconnected-(J5-5-PadCTS)") (class "Default")
      (node (ref "J5") (pin "CTS") (pinfunction "5_CTS") (pintype "passive"))
    )
    (net (code "50") (name "unconnected-(J6-1-PadDTR)") (class "Default")
      (node (ref "J6") (pin "DTR") (pinfunction "1_DTR") (pintype "passive"))
    )
    (net (code "51") (name "unconnected-(J6-5-PadCTS)") (class "Default")
      (node (ref "J6") (pin "CTS") (pinfunction "5_CTS") (pintype "passive"))
    )
    (net (code "52") (name "unconnected-(U1-NC-Pad4)") (class "Default")
      (node (ref "U1") (pin "4") (pinfunction "NC_4") (pintype "no_connect"))
    )
    (net (code "53") (name "unconnected-(U2-STAT-Pad1)") (class "Default")
      (node (ref "U2") (pin "1") (pinfunction "STAT_1") (pintype "bidirectional"))
    )
    (net (code "54") (name "unconnected-(U3-P0.02{slash}AIN0-Pad15)") (class "Default")
      (node (ref "U3") (pin "15") (pinfunction "P0.02/AIN0_15") (pintype "bidirectional"))
    )
    (net (code "55") (name "unconnected-(U3-P0.03{slash}AIN1-Pad16)") (class "Default")
      (node (ref "U3") (pin "16") (pinfunction "P0.03/AIN1_16") (pintype "bidirectional"))
    )
    (net (code "56") (name "unconnected-(U3-P0.04{slash}AIN2-Pad17)") (class "Default")
      (node (ref "U3") (pin "17") (pinfunction "P0.04/AIN2_17") (pintype "bidirectional"))
    )
    (net (code "57") (name "unconnected-(U3-P0.07-Pad20)") (class "Default")
      (node (ref "U3") (pin "20") (pinfunction "P0.07_20") (pintype "bidirectional"))
    )
    (net (code "58") (name "unconnected-(U3-P0.09-Pad22)") (class "Default")
      (node (ref "U3") (pin "22") (pinfunction "P0.09_22") (pintype "bidirectional"))
    )
    (net (code "59") (name "unconnected-(U3-P0.10-Pad23)") (class "Default")
      (node (ref "U3") (pin "23") (pinfunction "P0.10_23") (pintype "bidirectional"))
    )
    (net (code "60") (name "unconnected-(U3-P0.11-Pad25)") (class "Default")
      (node (ref "U3") (pin "25") (pinfunction "P0.11_25") (pintype "bidirectional"))
    )
    (net (code "61") (name "unconnected-(U3-P0.17-Pad31)") (class "Default")
      (node (ref "U3") (pin "31") (pinfunction "P0.17_31") (pintype "bidirectional"))
    )
    (net (code "62") (name "unconnected-(U3-P0.23-Pad41)") (class "Default")
      (node (ref "U3") (pin "41") (pinfunction "P0.23_41") (pintype "bidirectional"))
    )
    (net (code "63") (name "unconnected-(U3-P0.24-Pad40)") (class "Default")
      (node (ref "U3") (pin "40") (pinfunction "P0.24_40") (pintype "bidirectional"))
    )
    (net (code "64") (name "unconnected-(U3-P0.26-Pad3)") (class "Default")
      (node (ref "U3") (pin "3") (pinfunction "P0.26_3") (pintype "bidirectional"))
    )
    (net (code "65") (name "unconnected-(U4-NC-Pad4)") (class "Default")
      (node (ref "U4") (pin "4") (pinfunction "NC_4") (pintype "no_connect"))
    )
    (net (code "66") (name "unconnected-(U5-PadDIO1)") (class "Default")
      (node (ref "U5") (pin "DIO1") (pinfunction "DIO1_DIO1") (pintype "bidirectional"))
    )
    (net (code "67") (name "unconnected-(U5-PadDIO2)") (class "Default")
      (node (ref "U5") (pin "DIO2") (pinfunction "DIO2_DIO2") (pintype "bidirectional"))
    )
    (net (code "68") (name "unconnected-(U5-PadDIO3)") (class "Default")
      (node (ref "U5") (pin "DIO3") (pinfunction "DIO3_DIO3") (pintype "bidirectional"))
    )
    (net (code "69") (name "unconnected-(U5-PadDIO4)") (class "Default")
      (node (ref "U5") (pin "DIO4") (pinfunction "DIO4_DIO4") (pintype "bidirectional"))
    )
    (net (code "70") (name "unconnected-(U5-PadDIO5)") (class "Default")
      (node (ref "U5") (pin "DIO5") (pinfunction "DIO5_DIO5") (pintype "bidirectional"))
    )
    (net (code "71") (name "unconnected-(X2-ADC-Pad2)") (class "Default")
      (node (ref "X2") (pin "2") (pinfunction "ADC_2") (pintype "passive"))
    )
    (net (code "72") (name "unconnected-(X2-GPIO4-Pad14)") (class "Default")
      (node (ref "X2") (pin "14") (pinfunction "GPIO4_14") (pintype "bidirectional"))
    )
    (net (code "73") (name "unconnected-(X2-GPIO5-Pad13)") (class "Default")
      (node (ref "X2") (pin "13") (pinfunction "GPIO5_13") (pintype "bidirectional"))
    )
    (net (code "74") (name "unconnected-(X2-GPIO12-Pad6)") (class "Default")
      (node (ref "X2") (pin "6") (pinfunction "GPIO12_6") (pintype "bidirectional"))
    )
    (net (code "75") (name "unconnected-(X2-GPIO13-Pad7)") (class "Default")
      (node (ref "X2") (pin "7") (pinfunction "GPIO13_7") (pintype "bidirectional"))
    )
    (net (code "76") (name "unconnected-(X2-GPIO14-Pad5)") (class "Default")
      (node (ref "X2") (pin "5") (pinfunction "GPIO14_5") (pintype "bidirectional"))
    )
    (net (code "77") (name "unconnected-(X2-GPIO16-Pad4)") (class "Default")
      (node (ref "X2") (pin "4") (pinfunction "GPIO16_4") (pintype "bidirectional"))
    )
  )
)
